# Motor_Driver_THT.net
KiCad netlist of a schematic drawn in Altium Designer
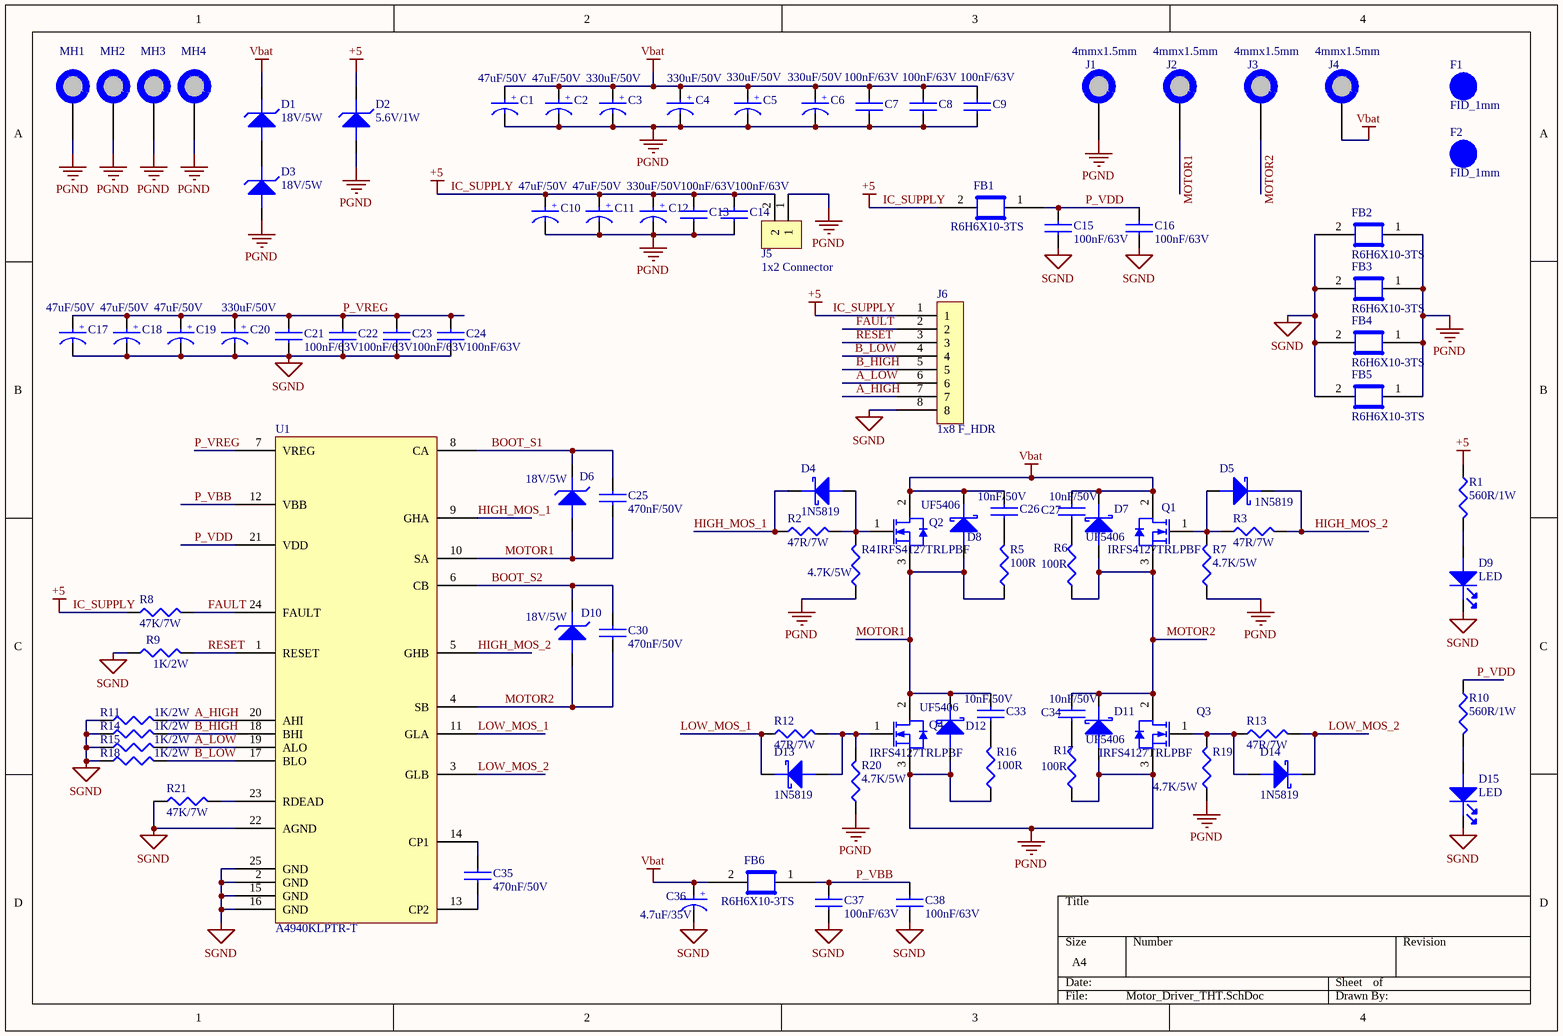
[diagram p0: Motor_Driver_THT.SchDoc]

(export (version "E")
  (design (tool "Eeschema 10.0.6"))
  (components
    (comp (ref "C1")
      (value "47uF/50V")
      (footprint "6.3x11x2.5Capacitor")
      (description "CAP.EL.47uF 50V 6x11 2.5mm")
      (libsource (lib "10A_Motor_Driver") (part "EXR470M50B"))
    )
    (comp (ref "C2")
      (value "47uF/50V")
      (footprint "6.3x11x2.5Capacitor")
      (description "CAP.EL.47uF 50V 6x11 2.5mm")
      (libsource (lib "10A_Motor_Driver") (part "EXR470M50B"))
    )
    (comp (ref "C3")
      (value "330uF/50V")
      (footprint "THT-CAP/10x16")
      (libsource (lib "10A_Motor_Driver") (part "TZP331M1HG25R-330uF Aluminium"))
    )
    (comp (ref "C4")
      (value "330uF/50V")
      (footprint "THT-CAP/10x16")
      (libsource (lib "10A_Motor_Driver") (part "TZP331M1HG25R-330uF Aluminium"))
    )
    (comp (ref "C5")
      (value "330uF/50V")
      (footprint "THT-CAP/10x16")
      (libsource (lib "10A_Motor_Driver") (part "TZP331M1HG25R-330uF Aluminium"))
    )
    (comp (ref "C6")
      (value "330uF/50V")
      (footprint "THT-CAP/10x16")
      (libsource (lib "10A_Motor_Driver") (part "TZP331M1HG25R-330uF Aluminium"))
    )
    (comp (ref "C7")
      (value "100nF/63V")
      (footprint "Film Cap")
      (description "Cap Film 0.1uF 63V PET 5% Stacked Radial 5mm 105°C Ammo Pack")
      (fields
        (field (name "MANUFACTURER") "Surge Components")
        (field (name "MANUFACTURER PART NUMBER") "C241J104J20A201")
      )
      (libsource (lib "10A_Motor_Driver") (part "C241J104J20A201"))
    )
    (comp (ref "C8")
      (value "100nF/63V")
      (footprint "Film Cap")
      (description "Cap Film 0.1uF 63V PET 5% Stacked Radial 5mm 105°C Ammo Pack")
      (fields
        (field (name "MANUFACTURER") "Surge Components")
        (field (name "MANUFACTURER PART NUMBER") "C241J104J20A201")
      )
      (libsource (lib "10A_Motor_Driver") (part "C241J104J20A201"))
    )
    (comp (ref "C9")
      (value "100nF/63V")
      (footprint "Film Cap")
      (description "Cap Film 0.1uF 63V PET 5% Stacked Radial 5mm 105°C Ammo Pack")
      (fields
        (field (name "MANUFACTURER") "Surge Components")
        (field (name "MANUFACTURER PART NUMBER") "C241J104J20A201")
      )
      (libsource (lib "10A_Motor_Driver") (part "C241J104J20A201"))
    )
    (comp (ref "C10")
      (value "47uF/50V")
      (footprint "6.3x11x2.5Capacitor")
      (description "CAP.EL.47uF 50V 6x11 2.5mm")
      (libsource (lib "10A_Motor_Driver") (part "EXR470M50B"))
    )
    (comp (ref "C11")
      (value "47uF/50V")
      (footprint "6.3x11x2.5Capacitor")
      (description "CAP.EL.47uF 50V 6x11 2.5mm")
      (libsource (lib "10A_Motor_Driver") (part "EXR470M50B"))
    )
    (comp (ref "C12")
      (value "330uF/50V")
      (footprint "THT-CAP/10x16")
      (libsource (lib "10A_Motor_Driver") (part "TZP331M1HG25R-330uF Aluminium"))
    )
    (comp (ref "C13")
      (value "100nF/63V")
      (footprint "Film Cap")
      (description "Cap Film 0.1uF 63V PET 5% Stacked Radial 5mm 105°C Ammo Pack")
      (fields
        (field (name "MANUFACTURER") "Surge Components")
        (field (name "MANUFACTURER PART NUMBER") "C241J104J20A201")
      )
      (libsource (lib "10A_Motor_Driver") (part "C241J104J20A201"))
    )
    (comp (ref "C14")
      (value "100nF/63V")
      (footprint "Film Cap")
      (description "Cap Film 0.1uF 63V PET 5% Stacked Radial 5mm 105°C Ammo Pack")
      (fields
        (field (name "MANUFACTURER") "Surge Components")
        (field (name "MANUFACTURER PART NUMBER") "C241J104J20A201")
      )
      (libsource (lib "10A_Motor_Driver") (part "C241J104J20A201"))
    )
    (comp (ref "C15")
      (value "100nF/63V")
      (footprint "CERAMIC CAP")
      (libsource (lib "10A_Motor_Driver") (part "DSTK2614"))
    )
    (comp (ref "C16")
      (value "100nF/63V")
      (footprint "CERAMIC CAP")
      (libsource (lib "10A_Motor_Driver") (part "DSTK2614"))
    )
    (comp (ref "C17")
      (value "47uF/50V")
      (footprint "6.3x11x2.5Capacitor")
      (description "CAP.EL.47uF 50V 6x11 2.5mm")
      (libsource (lib "10A_Motor_Driver") (part "EXR470M50B"))
    )
    (comp (ref "C18")
      (value "47uF/50V")
      (footprint "6.3x11x2.5Capacitor")
      (description "CAP.EL.47uF 50V 6x11 2.5mm")
      (libsource (lib "10A_Motor_Driver") (part "EXR470M50B"))
    )
    (comp (ref "C19")
      (value "47uF/50V")
      (footprint "6.3x11x2.5Capacitor")
      (description "CAP.EL.47uF 50V 6x11 2.5mm")
      (libsource (lib "10A_Motor_Driver") (part "EXR470M50B"))
    )
    (comp (ref "C20")
      (value "330uF/50V")
      (footprint "THT-CAP/10x16")
      (libsource (lib "10A_Motor_Driver") (part "TZP331M1HG25R-330uF Aluminium"))
    )
    (comp (ref "C21")
      (value "100nF/63V")
      (footprint "CERAMIC CAP")
      (libsource (lib "10A_Motor_Driver") (part "DSTK2614"))
    )
    (comp (ref "C22")
      (value "100nF/63V")
      (footprint "CERAMIC CAP")
      (libsource (lib "10A_Motor_Driver") (part "DSTK2614"))
    )
    (comp (ref "C23")
      (value "100nF/63V")
      (footprint "CERAMIC CAP")
      (libsource (lib "10A_Motor_Driver") (part "DSTK2614"))
    )
    (comp (ref "C24")
      (value "100nF/63V")
      (footprint "CERAMIC CAP")
      (libsource (lib "10A_Motor_Driver") (part "DSTK2614"))
    )
    (comp (ref "C25")
      (value "470nF/50V")
      (footprint "Film Cap")
      (libsource (lib "10A_Motor_Driver") (part "DSTK2594"))
    )
    (comp (ref "C26")
      (value "10nF/50V")
      (footprint "CERAMIC CAP")
      (libsource (lib "10A_Motor_Driver") (part "SF1H103MB215Y"))
    )
    (comp (ref "C27")
      (value "10nF/50V")
      (footprint "CERAMIC CAP")
      (libsource (lib "10A_Motor_Driver") (part "SF1H103MB215Y"))
    )
    (comp (ref "C30")
      (value "470nF/50V")
      (footprint "Film Cap")
      (libsource (lib "10A_Motor_Driver") (part "DSTK2594"))
    )
    (comp (ref "C33")
      (value "10nF/50V")
      (footprint "CERAMIC CAP")
      (libsource (lib "10A_Motor_Driver") (part "SF1H103MB215Y"))
    )
    (comp (ref "C34")
      (value "10nF/50V")
      (footprint "CERAMIC CAP")
      (libsource (lib "10A_Motor_Driver") (part "SF1H103MB215Y"))
    )
    (comp (ref "C35")
      (value "470nF/50V")
      (footprint "Film Cap")
      (libsource (lib "10A_Motor_Driver") (part "DSTK2594"))
    )
    (comp (ref "C36")
      (value "4.7uF/35V")
      (footprint "TANTALUM CAP THT 1")
      (libsource (lib "10A_Motor_Driver") (part "TKT4R7M3502BR"))
    )
    (comp (ref "C37")
      (value "100nF/63V")
      (footprint "CERAMIC CAP")
      (libsource (lib "10A_Motor_Driver") (part "DSTK2614"))
    )
    (comp (ref "C38")
      (value "100nF/63V")
      (footprint "CERAMIC CAP")
      (libsource (lib "10A_Motor_Driver") (part "DSTK2614"))
    )
    (comp (ref "D1")
      (value "18V/5W")
      (footprint "1N4745")
      (description "ON SEMICONDUCTOR   1N5355BRLG   DIODE, ZENER, 18V, 5W, 017AA-2")
      (fields
        (field (name "MANUFACTURER") "ON Semiconductor")
        (field (name "MANUFACTURER PART NUMBER") "1N5355BRLG")
      )
      (libsource (lib "10A_Motor_Driver") (part "1N5355BRLG"))
    )
    (comp (ref "D2")
      (value "5.6V/1W")
      (footprint "1N4745")
      (libsource (lib "10A_Motor_Driver") (part "1N4734A-HT"))
    )
    (comp (ref "D3")
      (value "18V/5W")
      (footprint "1N4745")
      (description "ON SEMICONDUCTOR   1N5355BRLG   DIODE, ZENER, 18V, 5W, 017AA-2")
      (fields
        (field (name "MANUFACTURER") "ON Semiconductor")
        (field (name "MANUFACTURER PART NUMBER") "1N5355BRLG")
      )
      (libsource (lib "10A_Motor_Driver") (part "1N5355BRLG"))
    )
    (comp (ref "D4")
      (value "1N5819")
      (footprint "1N5819")
      (fields
        (field (name "MANUFACTURER") "Pan Jit")
        (field (name "MANUFACTURER PART NUMBER") "1N5819_AY_10001")
      )
      (libsource (lib "10A_Motor_Driver") (part "1N5819_AY_10001"))
    )
    (comp (ref "D5")
      (value "1N5819")
      (footprint "1N5819")
      (fields
        (field (name "MANUFACTURER") "Pan Jit")
        (field (name "MANUFACTURER PART NUMBER") "1N5819_AY_10001")
      )
      (libsource (lib "10A_Motor_Driver") (part "1N5819_AY_10001"))
    )
    (comp (ref "D6")
      (value "18V/5W")
      (footprint "1N4745")
      (description "ON SEMICONDUCTOR   1N5355BRLG   DIODE, ZENER, 18V, 5W, 017AA-2")
      (fields
        (field (name "MANUFACTURER") "ON Semiconductor")
        (field (name "MANUFACTURER PART NUMBER") "1N5355BRLG")
      )
      (libsource (lib "10A_Motor_Driver") (part "1N5355BRLG"))
    )
    (comp (ref "D7")
      (value "UF5406")
      (footprint "UF5406")
      (libsource (lib "10A_Motor_Driver") (part "UF5406"))
    )
    (comp (ref "D8")
      (value "UF5406")
      (footprint "UF5406")
      (libsource (lib "10A_Motor_Driver") (part "UF5406"))
    )
    (comp (ref "D9")
      (value "LED")
      (footprint "5mm LED")
      (description "LED AMBER CLEAR 5MM ROUND T/H")
      (fields
        (field (name "MANUFACTURER") "Vishay Lite-On")
        (field (name "MANUFACTURER PART NUMBER") "LTL2R3SYK")
      )
      (libsource (lib "10A_Motor_Driver") (part "LTL2R3SYK"))
    )
    (comp (ref "D10")
      (value "18V/5W")
      (footprint "1N4745")
      (description "ON SEMICONDUCTOR   1N5355BRLG   DIODE, ZENER, 18V, 5W, 017AA-2")
      (fields
        (field (name "MANUFACTURER") "ON Semiconductor")
        (field (name "MANUFACTURER PART NUMBER") "1N5355BRLG")
      )
      (libsource (lib "10A_Motor_Driver") (part "1N5355BRLG"))
    )
    (comp (ref "D11")
      (value "UF5406")
      (footprint "UF5406")
      (libsource (lib "10A_Motor_Driver") (part "UF5406"))
    )
    (comp (ref "D12")
      (value "UF5406")
      (footprint "UF5406")
      (libsource (lib "10A_Motor_Driver") (part "UF5406"))
    )
    (comp (ref "D13")
      (value "1N5819")
      (footprint "1N5819")
      (fields
        (field (name "MANUFACTURER") "Pan Jit")
        (field (name "MANUFACTURER PART NUMBER") "1N5819_AY_10001")
      )
      (libsource (lib "10A_Motor_Driver") (part "1N5819_AY_10001"))
    )
    (comp (ref "D14")
      (value "1N5819")
      (footprint "1N5819")
      (fields
        (field (name "MANUFACTURER") "Pan Jit")
        (field (name "MANUFACTURER PART NUMBER") "1N5819_AY_10001")
      )
      (libsource (lib "10A_Motor_Driver") (part "1N5819_AY_10001"))
    )
    (comp (ref "D15")
      (value "LED")
      (footprint "5mm LED")
      (description "LED AMBER CLEAR 5MM ROUND T/H")
      (fields
        (field (name "MANUFACTURER") "Vishay Lite-On")
        (field (name "MANUFACTURER PART NUMBER") "LTL2R3SYK")
      )
      (libsource (lib "10A_Motor_Driver") (part "LTL2R3SYK"))
    )
    (comp (ref "F1")
      (value "FID_1mm")
      (footprint "FID_40x120D")
      (description "Fiducial 40mil Diameter, 120mil mask")
      (libsource (lib "10A_Motor_Driver") (part "FID_1mm"))
    )
    (comp (ref "F2")
      (value "FID_1mm")
      (footprint "FID_40x120D")
      (description "Fiducial 40mil Diameter, 120mil mask")
      (libsource (lib "10A_Motor_Driver") (part "FID_1mm"))
    )
    (comp (ref "FB1")
      (value "R6H6X10-3TS")
      (footprint "1N4745")
      (libsource (lib "10A_Motor_Driver") (part "R6H6X10-3TS"))
    )
    (comp (ref "FB2")
      (value "R6H6X10-3TS")
      (footprint "1N4745")
      (libsource (lib "10A_Motor_Driver") (part "R6H6X10-3TS"))
    )
    (comp (ref "FB3")
      (value "R6H6X10-3TS")
      (footprint "1N4745")
      (libsource (lib "10A_Motor_Driver") (part "R6H6X10-3TS"))
    )
    (comp (ref "FB4")
      (value "R6H6X10-3TS")
      (footprint "1N4745")
      (libsource (lib "10A_Motor_Driver") (part "R6H6X10-3TS"))
    )
    (comp (ref "FB5")
      (value "R6H6X10-3TS")
      (footprint "1N4745")
      (libsource (lib "10A_Motor_Driver") (part "R6H6X10-3TS"))
    )
    (comp (ref "FB6")
      (value "R6H6X10-3TS")
      (footprint "1N4745")
      (libsource (lib "10A_Motor_Driver") (part "R6H6X10-3TS"))
    )
    (comp (ref "J1")
      (value "4mmx1.5mm")
      (footprint "PAD_WITH_HOLE_4mmx1.5mm")
      (description "PAD_WITH_HOLE_4mmx1.5mm")
      (libsource (lib "10A_Motor_Driver") (part "PAD_WITH_HOLE_4mmx1.5mm"))
    )
    (comp (ref "J2")
      (value "4mmx1.5mm")
      (footprint "PAD_WITH_HOLE_4mmx1.5mm")
      (description "PAD_WITH_HOLE_4mmx1.5mm")
      (libsource (lib "10A_Motor_Driver") (part "PAD_WITH_HOLE_4mmx1.5mm"))
    )
    (comp (ref "J3")
      (value "4mmx1.5mm")
      (footprint "PAD_WITH_HOLE_4mmx1.5mm")
      (description "PAD_WITH_HOLE_4mmx1.5mm")
      (libsource (lib "10A_Motor_Driver") (part "PAD_WITH_HOLE_4mmx1.5mm"))
    )
    (comp (ref "J4")
      (value "4mmx1.5mm")
      (footprint "PAD_WITH_HOLE_4mmx1.5mm")
      (description "PAD_WITH_HOLE_4mmx1.5mm")
      (libsource (lib "10A_Motor_Driver") (part "PAD_WITH_HOLE_4mmx1.5mm"))
    )
    (comp (ref "J5")
      (value "1x2 Connector")
      (footprint "Klemens 1x2")
      (libsource (lib "10A_Motor_Driver") (part "Klemens 2 Pin"))
    )
    (comp (ref "J6")
      (value "1x8 F_HDR")
      (footprint "1x8 2.54 mm F_HDR")
      (libsource (lib "10A_Motor_Driver") (part "1X8 F_HDR 2.54mm"))
    )
    (comp (ref "MH1")
      (value "MOUNTING HOLE_7.4MMC_3.2MMD")
      (footprint "MH_7.2MMC_3.2MMD")
      (description "Mounting Hole  7.4mm, 3.2mm")
      (libsource (lib "10A_Motor_Driver") (part "MOUNTING HOLE_7.4MMC_3.2MMD"))
    )
    (comp (ref "MH2")
      (value "MOUNTING HOLE_7.4MMC_3.2MMD")
      (footprint "MH_7.2MMC_3.2MMD")
      (description "Mounting Hole  7.4mm, 3.2mm")
      (libsource (lib "10A_Motor_Driver") (part "MOUNTING HOLE_7.4MMC_3.2MMD"))
    )
    (comp (ref "MH3")
      (value "MOUNTING HOLE_7.4MMC_3.2MMD")
      (footprint "MH_7.2MMC_3.2MMD")
      (description "Mounting Hole  7.4mm, 3.2mm")
      (libsource (lib "10A_Motor_Driver") (part "MOUNTING HOLE_7.4MMC_3.2MMD"))
    )
    (comp (ref "MH4")
      (value "MOUNTING HOLE_7.4MMC_3.2MMD")
      (footprint "MH_7.2MMC_3.2MMD")
      (description "Mounting Hole  7.4mm, 3.2mm")
      (libsource (lib "10A_Motor_Driver") (part "MOUNTING HOLE_7.4MMC_3.2MMD"))
    )
    (comp (ref "Q1")
      (value "IRFS4127TRLPBF")
      (footprint "TO-220")
      (description "MOSFET N-CH 200V 72A D2PAK")
      (fields (field (name "MANUFACTURER") "International Rectifier"))
      (libsource (lib "10A_Motor_Driver") (part "IRFS4127TRLPBF"))
    )
    (comp (ref "Q2")
      (value "IRFS4127TRLPBF")
      (footprint "TO-220")
      (description "MOSFET N-CH 200V 72A D2PAK")
      (fields (field (name "MANUFACTURER") "International Rectifier"))
      (libsource (lib "10A_Motor_Driver") (part "IRFS4127TRLPBF"))
    )
    (comp (ref "Q3")
      (value "IRFS4127TRLPBF")
      (footprint "TO-220")
      (description "MOSFET N-CH 200V 72A D2PAK")
      (fields (field (name "MANUFACTURER") "International Rectifier"))
      (libsource (lib "10A_Motor_Driver") (part "IRFS4127TRLPBF"))
    )
    (comp (ref "Q4")
      (value "IRFS4127TRLPBF")
      (footprint "TO-220")
      (description "MOSFET N-CH 200V 72A D2PAK")
      (fields (field (name "MANUFACTURER") "International Rectifier"))
      (libsource (lib "10A_Motor_Driver") (part "IRFS4127TRLPBF"))
    )
    (comp (ref "R1")
      (value "560R/1W")
      (footprint "THT Resistor")
      (libsource (lib "10A_Motor_Driver") (part "KNP01SJ0561A10"))
    )
    (comp (ref "R2")
      (value "47R/7W")
      (footprint "THT Resistor")
      (libsource (lib "10A_Motor_Driver") (part "RSS700470JB60"))
    )
    (comp (ref "R3")
      (value "47R/7W")
      (footprint "THT Resistor")
      (libsource (lib "10A_Motor_Driver") (part "RSS700470JB60"))
    )
    (comp (ref "R4")
      (value "4.7K/5W")
      (footprint "THT Resistor")
      (libsource (lib "10A_Motor_Driver") (part "MOR05UJ0472AA9"))
    )
    (comp (ref "R5")
      (value "100R")
      (footprint "THT Resistor")
      (libsource (lib "10A_Motor_Driver") (part "KNP09SJ0101B00"))
    )
    (comp (ref "R6")
      (value "100R")
      (footprint "THT Resistor")
      (libsource (lib "10A_Motor_Driver") (part "KNP09SJ0101B00"))
    )
    (comp (ref "R7")
      (value "4.7K/5W")
      (footprint "THT Resistor")
      (libsource (lib "10A_Motor_Driver") (part "MOR05UJ0472AA9"))
    )
    (comp (ref "R8")
      (value "47K/7W")
      (footprint "THT Resistor")
      (fields
        (field (name "MANUFACTURER") "Royal Ohm")
        (field (name "MANUFACTURER PART NUMBER") "MOR07SJ0473B00")
      )
      (libsource (lib "10A_Motor_Driver") (part "MOR07SJ0473B00"))
    )
    (comp (ref "R9")
      (value "1K/2W")
      (footprint "THT Resistor")
      (libsource (lib "10A_Motor_Driver") (part "CFRF2SJ0102A19"))
    )
    (comp (ref "R10")
      (value "560R/1W")
      (footprint "THT Resistor")
      (libsource (lib "10A_Motor_Driver") (part "KNP01SJ0561A10"))
    )
    (comp (ref "R11")
      (value "1K/2W")
      (footprint "THT Resistor")
      (libsource (lib "10A_Motor_Driver") (part "CFRF2SJ0102A19"))
    )
    (comp (ref "R12")
      (value "47R/7W")
      (footprint "THT Resistor")
      (libsource (lib "10A_Motor_Driver") (part "RSS700470JB60"))
    )
    (comp (ref "R13")
      (value "47R/7W")
      (footprint "THT Resistor")
      (libsource (lib "10A_Motor_Driver") (part "RSS700470JB60"))
    )
    (comp (ref "R14")
      (value "1K/2W")
      (footprint "THT Resistor")
      (libsource (lib "10A_Motor_Driver") (part "CFRF2SJ0102A19"))
    )
    (comp (ref "R15")
      (value "1K/2W")
      (footprint "THT Resistor")
      (libsource (lib "10A_Motor_Driver") (part "CFRF2SJ0102A19"))
    )
    (comp (ref "R16")
      (value "100R")
      (footprint "THT Resistor")
      (libsource (lib "10A_Motor_Driver") (part "KNP09SJ0101B00"))
    )
    (comp (ref "R17")
      (value "100R")
      (footprint "THT Resistor")
      (libsource (lib "10A_Motor_Driver") (part "KNP09SJ0101B00"))
    )
    (comp (ref "R18")
      (value "1K/2W")
      (footprint "THT Resistor")
      (libsource (lib "10A_Motor_Driver") (part "CFRF2SJ0102A19"))
    )
    (comp (ref "R19")
      (value "4.7K/5W")
      (footprint "THT Resistor")
      (libsource (lib "10A_Motor_Driver") (part "MOR05UJ0472AA9"))
    )
    (comp (ref "R20")
      (value "4.7K/5W")
      (footprint "THT Resistor")
      (libsource (lib "10A_Motor_Driver") (part "MOR05UJ0472AA9"))
    )
    (comp (ref "R21")
      (value "47K/7W")
      (footprint "THT Resistor")
      (fields
        (field (name "MANUFACTURER") "Royal Ohm")
        (field (name "MANUFACTURER PART NUMBER") "MOR07SJ0473B00")
      )
      (libsource (lib "10A_Motor_Driver") (part "MOR07SJ0473B00"))
    )
    (comp (ref "U1")
      (value "A4940KLPTR-T")
      (footprint "A4940-TSOP65P640X120_HS-25N")
      (description "IC MOSF DVR FULL BRIDGE 24TSSOP")
      (fields (field (name "MANUFACTURER") "Allegro MicroSystems"))
      (libsource (lib "10A_Motor_Driver") (part "A4940KLPTR-T"))
    )
  )
  (nets
    (net (code "1") (name "+5") (class "Default")
      (node (ref "C10") (pin "1") (pinfunction "1_1") (pintype "passive"))
      (node (ref "C11") (pin "1") (pinfunction "1_1") (pintype "passive"))
      (node (ref "C12") (pin "1") (pinfunction "1_1") (pintype "passive"))
      (node (ref "C13") (pin "2") (pinfunction "2_2") (pintype "passive"))
      (node (ref "C14") (pin "2") (pinfunction "2_2") (pintype "passive"))
      (node (ref "D2") (pin "1") (pinfunction "Cathode_1") (pintype "passive"))
      (node (ref "FB1") (pin "2") (pinfunction "2_2") (pintype "passive"))
      (node (ref "J5") (pin "2") (pinfunction "2_2") (pintype "passive"))
      (node (ref "J6") (pin "1") (pinfunction "1_1") (pintype "passive"))
      (node (ref "R1") (pin "1") (pinfunction "1_1") (pintype "passive"))
      (node (ref "R8") (pin "1") (pinfunction "1_1") (pintype "passive"))
    )
    (net (code "2") (name "/A_HIGH") (class "Default")
      (node (ref "J6") (pin "7") (pinfunction "7_7") (pintype "passive"))
      (node (ref "R11") (pin "2") (pinfunction "2_2") (pintype "passive"))
      (node (ref "U1") (pin "20") (pinfunction "AHI_20") (pintype "passive"))
    )
    (net (code "3") (name "/A_LOW") (class "Default")
      (node (ref "J6") (pin "6") (pinfunction "6_6") (pintype "passive"))
      (node (ref "R15") (pin "2") (pinfunction "2_2") (pintype "passive"))
      (node (ref "U1") (pin "19") (pinfunction "ALO_19") (pintype "passive"))
    )
    (net (code "4") (name "/BOOT_S1") (class "Default")
      (node (ref "C25") (pin "2") (pinfunction "2_2") (pintype "passive"))
      (node (ref "D6") (pin "1") (pinfunction "Cathode_1") (pintype "passive"))
      (node (ref "U1") (pin "8") (pinfunction "CA_8") (pintype "passive"))
    )
    (net (code "5") (name "/BOOT_S2") (class "Default")
      (node (ref "C30") (pin "2") (pinfunction "2_2") (pintype "passive"))
      (node (ref "D10") (pin "1") (pinfunction "Cathode_1") (pintype "passive"))
      (node (ref "U1") (pin "6") (pinfunction "CB_6") (pintype "passive"))
    )
    (net (code "6") (name "/B_HIGH") (class "Default")
      (node (ref "J6") (pin "5") (pinfunction "5_5") (pintype "passive"))
      (node (ref "R14") (pin "2") (pinfunction "2_2") (pintype "passive"))
      (node (ref "U1") (pin "18") (pinfunction "BHI_18") (pintype "passive"))
    )
    (net (code "7") (name "/B_LOW") (class "Default")
      (node (ref "J6") (pin "4") (pinfunction "4_4") (pintype "passive"))
      (node (ref "R18") (pin "2") (pinfunction "2_2") (pintype "passive"))
      (node (ref "U1") (pin "17") (pinfunction "BLO_17") (pintype "passive"))
    )
    (net (code "8") (name "/FAULT") (class "Default")
      (node (ref "J6") (pin "2") (pinfunction "2_2") (pintype "passive"))
      (node (ref "R8") (pin "2") (pinfunction "2_2") (pintype "passive"))
      (node (ref "U1") (pin "24") (pinfunction "FAULT_24") (pintype "passive"))
    )
    (net (code "9") (name "/HIGH_MOS_1") (class "Default")
      (node (ref "D4") (pin "1") (pinfunction "Cathode_1") (pintype "passive"))
      (node (ref "R2") (pin "1") (pinfunction "1_1") (pintype "passive"))
      (node (ref "U1") (pin "9") (pinfunction "GHA_9") (pintype "passive"))
    )
    (net (code "10") (name "/HIGH_MOS_2") (class "Default")
      (node (ref "D5") (pin "1") (pinfunction "Cathode_1") (pintype "passive"))
      (node (ref "R3") (pin "2") (pinfunction "2_2") (pintype "passive"))
      (node (ref "U1") (pin "5") (pinfunction "GHB_5") (pintype "passive"))
    )
    (net (code "11") (name "/LOW_MOS_1") (class "Default")
      (node (ref "D13") (pin "1") (pinfunction "Cathode_1") (pintype "passive"))
      (node (ref "R12") (pin "1") (pinfunction "1_1") (pintype "passive"))
      (node (ref "U1") (pin "11") (pinfunction "GLA_11") (pintype "passive"))
    )
    (net (code "12") (name "/LOW_MOS_2") (class "Default")
      (node (ref "D14") (pin "1") (pinfunction "Cathode_1") (pintype "passive"))
      (node (ref "R13") (pin "2") (pinfunction "2_2") (pintype "passive"))
      (node (ref "U1") (pin "3") (pinfunction "GLB_3") (pintype "passive"))
    )
    (net (code "13") (name "/MOTOR1") (class "Default")
      (node (ref "C25") (pin "1") (pinfunction "1_1") (pintype "passive"))
      (node (ref "C33") (pin "2") (pinfunction "2_2") (pintype "passive"))
      (node (ref "D12") (pin "1") (pinfunction "Cathode_1") (pintype "passive"))
      (node (ref "D6") (pin "2") (pinfunction "Anode_2") (pintype "passive"))
      (node (ref "D8") (pin "2") (pinfunction "Anode_2") (pintype "passive"))
      (node (ref "J2") (pin "1") (pinfunction "1_1") (pintype "passive"))
      (node (ref "Q2") (pin "3") (pinfunction "SOURCE_3") (pintype "passive"))
      (node (ref "Q4") (pin "2") (pinfunction "DRAIN_2") (pintype "passive"))
      (node (ref "R5") (pin "1") (pinfunction "1_1") (pintype "passive"))
      (node (ref "U1") (pin "10") (pinfunction "SA_10") (pintype "passive"))
    )
    (net (code "14") (name "/MOTOR2") (class "Default")
      (node (ref "C30") (pin "1") (pinfunction "1_1") (pintype "passive"))
      (node (ref "C34") (pin "2") (pinfunction "2_2") (pintype "passive"))
      (node (ref "D10") (pin "2") (pinfunction "Anode_2") (pintype "passive"))
      (node (ref "D11") (pin "1") (pinfunction "Cathode_1") (pintype "passive"))
      (node (ref "D7") (pin "2") (pinfunction "Anode_2") (pintype "passive"))
      (node (ref "J3") (pin "1") (pinfunction "1_1") (pintype "passive"))
      (node (ref "Q1") (pin "3") (pinfunction "SOURCE_3") (pintype "passive"))
      (node (ref "Q3") (pin "2") (pinfunction "DRAIN_2") (pintype "passive"))
      (node (ref "R6") (pin "1") (pinfunction "1_1") (pintype "passive"))
      (node (ref "U1") (pin "4") (pinfunction "SB_4") (pintype "passive"))
    )
    (net (code "15") (name "/P_VBB") (class "Default")
      (node (ref "C37") (pin "2") (pinfunction "2_2") (pintype "passive"))
      (node (ref "C38") (pin "2") (pinfunction "2_2") (pintype "passive"))
      (node (ref "FB6") (pin "1") (pinfunction "1_1") (pintype "passive"))
      (node (ref "U1") (pin "12") (pinfunction "VBB_12") (pintype "passive"))
    )
    (net (code "16") (name "/P_VDD") (class "Default")
      (node (ref "C15") (pin "2") (pinfunction "2_2") (pintype "passive"))
      (node (ref "C16") (pin "2") (pinfunction "2_2") (pintype "passive"))
      (node (ref "FB1") (pin "1") (pinfunction "1_1") (pintype "passive"))
      (node (ref "R10") (pin "1") (pinfunction "1_1") (pintype "passive"))
      (node (ref "U1") (pin "21") (pinfunction "VDD_21") (pintype "passive"))
    )
    (net (code "17") (name "/P_VREG") (class "Default")
      (node (ref "C17") (pin "1") (pinfunction "1_1") (pintype "passive"))
      (node (ref "C18") (pin "1") (pinfunction "1_1") (pintype "passive"))
      (node (ref "C19") (pin "1") (pinfunction "1_1") (pintype "passive"))
      (node (ref "C20") (pin "1") (pinfunction "1_1") (pintype "passive"))
      (node (ref "C21") (pin "2") (pinfunction "2_2") (pintype "passive"))
      (node (ref "C22") (pin "2") (pinfunction "2_2") (pintype "passive"))
      (node (ref "C23") (pin "2") (pinfunction "2_2") (pintype "passive"))
      (node (ref "C24") (pin "2") (pinfunction "2_2") (pintype "passive"))
      (node (ref "U1") (pin "7") (pinfunction "VREG_7") (pintype "passive"))
    )
    (net (code "18") (name "/RESET") (class "Default")
      (node (ref "J6") (pin "3") (pinfunction "3_3") (pintype "passive"))
      (node (ref "R9") (pin "2") (pinfunction "2_2") (pintype "passive"))
      (node (ref "U1") (pin "1") (pinfunction "RESET_1") (pintype "passive"))
    )
    (net (code "19") (name "Net-(C26-Pad1)") (class "Default")
      (node (ref "C26") (pin "1") (pinfunction "1_1") (pintype "passive"))
      (node (ref "R5") (pin "2") (pinfunction "2_2") (pintype "passive"))
    )
    (net (code "20") (name "Net-(C27-Pad1)") (class "Default")
      (node (ref "C27") (pin "1") (pinfunction "1_1") (pintype "passive"))
      (node (ref "R6") (pin "2") (pinfunction "2_2") (pintype "passive"))
    )
    (net (code "21") (name "Net-(C33-Pad1)") (class "Default")
      (node (ref "C33") (pin "1") (pinfunction "1_1") (pintype "passive"))
      (node (ref "R16") (pin "2") (pinfunction "2_2") (pintype "passive"))
    )
    (net (code "22") (name "Net-(C34-Pad1)") (class "Default")
      (node (ref "C34") (pin "1") (pinfunction "1_1") (pintype "passive"))
      (node (ref "R17") (pin "2") (pinfunction "2_2") (pintype "passive"))
    )
    (net (code "23") (name "Net-(D1-Anode)") (class "Default")
      (node (ref "D1") (pin "2") (pinfunction "Anode_2") (pintype "passive"))
      (node (ref "D3") (pin "1") (pinfunction "Cathode_1") (pintype "passive"))
    )
    (net (code "24") (name "Net-(D4-Anode)") (class "Default")
      (node (ref "D4") (pin "2") (pinfunction "Anode_2") (pintype "passive"))
      (node (ref "Q2") (pin "1") (pinfunction "GATE_1") (pintype "passive"))
      (node (ref "R2") (pin "2") (pinfunction "2_2") (pintype "passive"))
      (node (ref "R4") (pin "2") (pinfunction "2_2") (pintype "passive"))
    )
    (net (code "25") (name "Net-(D5-Anode)") (class "Default")
      (node (ref "D5") (pin "2") (pinfunction "Anode_2") (pintype "passive"))
      (node (ref "Q1") (pin "1") (pinfunction "GATE_1") (pintype "passive"))
      (node (ref "R3") (pin "1") (pinfunction "1_1") (pintype "passive"))
      (node (ref "R7") (pin "2") (pinfunction "2_2") (pintype "passive"))
    )
    (net (code "26") (name "Net-(D9-Anode)") (class "Default")
      (node (ref "D9") (pin "2") (pinfunction "Anode_2") (pintype "passive"))
      (node (ref "R1") (pin "2") (pinfunction "2_2") (pintype "passive"))
    )
    (net (code "27") (name "Net-(D13-Anode)") (class "Default")
      (node (ref "D13") (pin "2") (pinfunction "Anode_2") (pintype "passive"))
      (node (ref "Q4") (pin "1") (pinfunction "GATE_1") (pintype "passive"))
      (node (ref "R12") (pin "2") (pinfunction "2_2") (pintype "passive"))
      (node (ref "R20") (pin "2") (pinfunction "2_2") (pintype "passive"))
    )
    (net (code "28") (name "Net-(D14-Anode)") (class "Default")
      (node (ref "D14") (pin "2") (pinfunction "Anode_2") (pintype "passive"))
      (node (ref "Q3") (pin "1") (pinfunction "GATE_1") (pintype "passive"))
      (node (ref "R13") (pin "1") (pinfunction "1_1") (pintype "passive"))
      (node (ref "R19") (pin "2") (pinfunction "2_2") (pintype "passive"))
    )
    (net (code "29") (name "Net-(D15-Anode)") (class "Default")
      (node (ref "D15") (pin "2") (pinfunction "Anode_2") (pintype "passive"))
      (node (ref "R10") (pin "2") (pinfunction "2_2") (pintype "passive"))
    )
    (net (code "30") (name "Net-(U1-CP1)") (class "Default")
      (node (ref "C35") (pin "2") (pinfunction "2_2") (pintype "passive"))
      (node (ref "U1") (pin "14") (pinfunction "CP1_14") (pintype "passive"))
    )
    (net (code "31") (name "Net-(U1-CP2)") (class "Default")
      (node (ref "C35") (pin "1") (pinfunction "1_1") (pintype "passive"))
      (node (ref "U1") (pin "13") (pinfunction "CP2_13") (pintype "passive"))
    )
    (net (code "32") (name "Net-(U1-RDEAD)") (class "Default")
      (node (ref "R21") (pin "2") (pinfunction "2_2") (pintype "passive"))
      (node (ref "U1") (pin "23") (pinfunction "RDEAD_23") (pintype "passive"))
    )
    (net (code "33") (name "PGND") (class "Default")
      (node (ref "C1") (pin "2") (pinfunction "2_2") (pintype "passive"))
      (node (ref "C10") (pin "2") (pinfunction "2_2") (pintype "passive"))
      (node (ref "C11") (pin "2") (pinfunction "2_2") (pintype "passive"))
      (node (ref "C12") (pin "2") (pinfunction "2_2") (pintype "passive"))
      (node (ref "C13") (pin "1") (pinfunction "1_1") (pintype "passive"))
      (node (ref "C14") (pin "1") (pinfunction "1_1") (pintype "passive"))
      (node (ref "C2") (pin "2") (pinfunction "2_2") (pintype "passive"))
      (node (ref "C3") (pin "2") (pinfunction "2_2") (pintype "passive"))
      (node (ref "C4") (pin "2") (pinfunction "2_2") (pintype "passive"))
      (node (ref "C5") (pin "2") (pinfunction "2_2") (pintype "passive"))
      (node (ref "C6") (pin "2") (pinfunction "2_2") (pintype "passive"))
      (node (ref "C7") (pin "2") (pinfunction "2_2") (pintype "passive"))
      (node (ref "C8") (pin "2") (pinfunction "2_2") (pintype "passive"))
      (node (ref "C9") (pin "2") (pinfunction "2_2") (pintype "passive"))
      (node (ref "D11") (pin "2") (pinfunction "Anode_2") (pintype "passive"))
      (node (ref "D12") (pin "2") (pinfunction "Anode_2") (pintype "passive"))
      (node (ref "D2") (pin "2") (pinfunction "Anode_2") (pintype "passive"))
      (node (ref "D3") (pin "2") (pinfunction "Anode_2") (pintype "passive"))
      (node (ref "FB2") (pin "1") (pinfunction "1_1") (pintype "passive"))
      (node (ref "FB3") (pin "1") (pinfunction "1_1") (pintype "passive"))
      (node (ref "FB4") (pin "1") (pinfunction "1_1") (pintype "passive"))
      (node (ref "FB5") (pin "1") (pinfunction "1_1") (pintype "passive"))
      (node (ref "J1") (pin "1") (pinfunction "1_1") (pintype "passive"))
      (node (ref "J5") (pin "1") (pinfunction "1_1") (pintype "passive"))
      (node (ref "MH1") (pin "1") (pinfunction "1_1") (pintype "passive"))
      (node (ref "MH2") (pin "1") (pinfunction "1_1") (pintype "passive"))
      (node (ref "MH3") (pin "1") (pinfunction "1_1") (pintype "passive"))
      (node (ref "MH4") (pin "1") (pinfunction "1_1") (pintype "passive"))
      (node (ref "Q3") (pin "3") (pinfunction "SOURCE_3") (pintype "passive"))
      (node (ref "Q4") (pin "3") (pinfunction "SOURCE_3") (pintype "passive"))
      (node (ref "R16") (pin "1") (pinfunction "1_1") (pintype "passive"))
      (node (ref "R17") (pin "1") (pinfunction "1_1") (pintype "passive"))
      (node (ref "R19") (pin "1") (pinfunction "1_1") (pintype "passive"))
      (node (ref "R20") (pin "1") (pinfunction "1_1") (pintype "passive"))
      (node (ref "R4") (pin "1") (pinfunction "1_1") (pintype "passive"))
      (node (ref "R7") (pin "1") (pinfunction "1_1") (pintype "passive"))
    )
    (net (code "34") (name "SGND") (class "Default")
      (node (ref "C15") (pin "1") (pinfunction "1_1") (pintype "passive"))
      (node (ref "C16") (pin "1") (pinfunction "1_1") (pintype "passive"))
      (node (ref "C17") (pin "2") (pinfunction "2_2") (pintype "passive"))
      (node (ref "C18") (pin "2") (pinfunction "2_2") (pintype "passive"))
      (node (ref "C19") (pin "2") (pinfunction "2_2") (pintype "passive"))
      (node (ref "C20") (pin "2") (pinfunction "2_2") (pintype "passive"))
      (node (ref "C21") (pin "1") (pinfunction "1_1") (pintype "passive"))
      (node (ref "C22") (pin "1") (pinfunction "1_1") (pintype "passive"))
      (node (ref "C23") (pin "1") (pinfunction "1_1") (pintype "passive"))
      (node (ref "C24") (pin "1") (pinfunction "1_1") (pintype "passive"))
      (node (ref "C36") (pin "2") (pinfunction "2_2") (pintype "passive"))
      (node (ref "C37") (pin "1") (pinfunction "1_1") (pintype "passive"))
      (node (ref "C38") (pin "1") (pinfunction "1_1") (pintype "passive"))
      (node (ref "D15") (pin "1") (pinfunction "Cathode_1") (pintype "passive"))
      (node (ref "D9") (pin "1") (pinfunction "Cathode_1") (pintype "passive"))
      (node (ref "FB2") (pin "2") (pinfunction "2_2") (pintype "passive"))
      (node (ref "FB3") (pin "2") (pinfunction "2_2") (pintype "passive"))
      (node (ref "FB4") (pin "2") (pinfunction "2_2") (pintype "passive"))
      (node (ref "FB5") (pin "2") (pinfunction "2_2") (pintype "passive"))
      (node (ref "J6") (pin "8") (pinfunction "8_8") (pintype "passive"))
      (node (ref "R11") (pin "1") (pinfunction "1_1") (pintype "passive"))
      (node (ref "R14") (pin "1") (pinfunction "1_1") (pintype "passive"))
      (node (ref "R15") (pin "1") (pinfunction "1_1") (pintype "passive"))
      (node (ref "R18") (pin "1") (pinfunction "1_1") (pintype "passive"))
      (node (ref "R21") (pin "1") (pinfunction "1_1") (pintype "passive"))
      (node (ref "R9") (pin "1") (pinfunction "1_1") (pintype "passive"))
      (node (ref "U1") (pin "15") (pinfunction "GND_15") (pintype "passive"))
      (node (ref "U1") (pin "16") (pinfunction "GND_16") (pintype "passive"))
      (node (ref "U1") (pin "2") (pinfunction "GND_2") (pintype "passive"))
      (node (ref "U1") (pin "22") (pinfunction "AGND_22") (pintype "passive"))
      (node (ref "U1") (pin "25") (pinfunction "GND_25") (pintype "passive"))
    )
    (net (code "35") (name "Vbat") (class "Default")
      (node (ref "C1") (pin "1") (pinfunction "1_1") (pintype "passive"))
      (node (ref "C2") (pin "1") (pinfunction "1_1") (pintype "passive"))
      (node (ref "C26") (pin "2") (pinfunction "2_2") (pintype "passive"))
      (node (ref "C27") (pin "2") (pinfunction "2_2") (pintype "passive"))
      (node (ref "C3") (pin "1") (pinfunction "1_1") (pintype "passive"))
      (node (ref "C36") (pin "1") (pinfunction "1_1") (pintype "passive"))
      (node (ref "C4") (pin "1") (pinfunction "1_1") (pintype "passive"))
      (node (ref "C5") (pin "1") (pinfunction "1_1") (pintype "passive"))
      (node (ref "C6") (pin "1") (pinfunction "1_1") (pintype "passive"))
      (node (ref "C7") (pin "1") (pinfunction "1_1") (pintype "passive"))
      (node (ref "C8") (pin "1") (pinfunction "1_1") (pintype "passive"))
      (node (ref "C9") (pin "1") (pinfunction "1_1") (pintype "passive"))
      (node (ref "D1") (pin "1") (pinfunction "Cathode_1") (pintype "passive"))
      (node (ref "D7") (pin "1") (pinfunction "Cathode_1") (pintype "passive"))
      (node (ref "D8") (pin "1") (pinfunction "Cathode_1") (pintype "passive"))
      (node (ref "FB6") (pin "2") (pinfunction "2_2") (pintype "passive"))
      (node (ref "J4") (pin "1") (pinfunction "1_1") (pintype "passive"))
      (node (ref "Q1") (pin "2") (pinfunction "DRAIN_2") (pintype "passive"))
      (node (ref "Q2") (pin "2") (pinfunction "DRAIN_2") (pintype "passive"))
    )
  )
)
